# MB_Digital_and_Aanalog.net
KiCad netlist of a schematic drawn in EAGLE
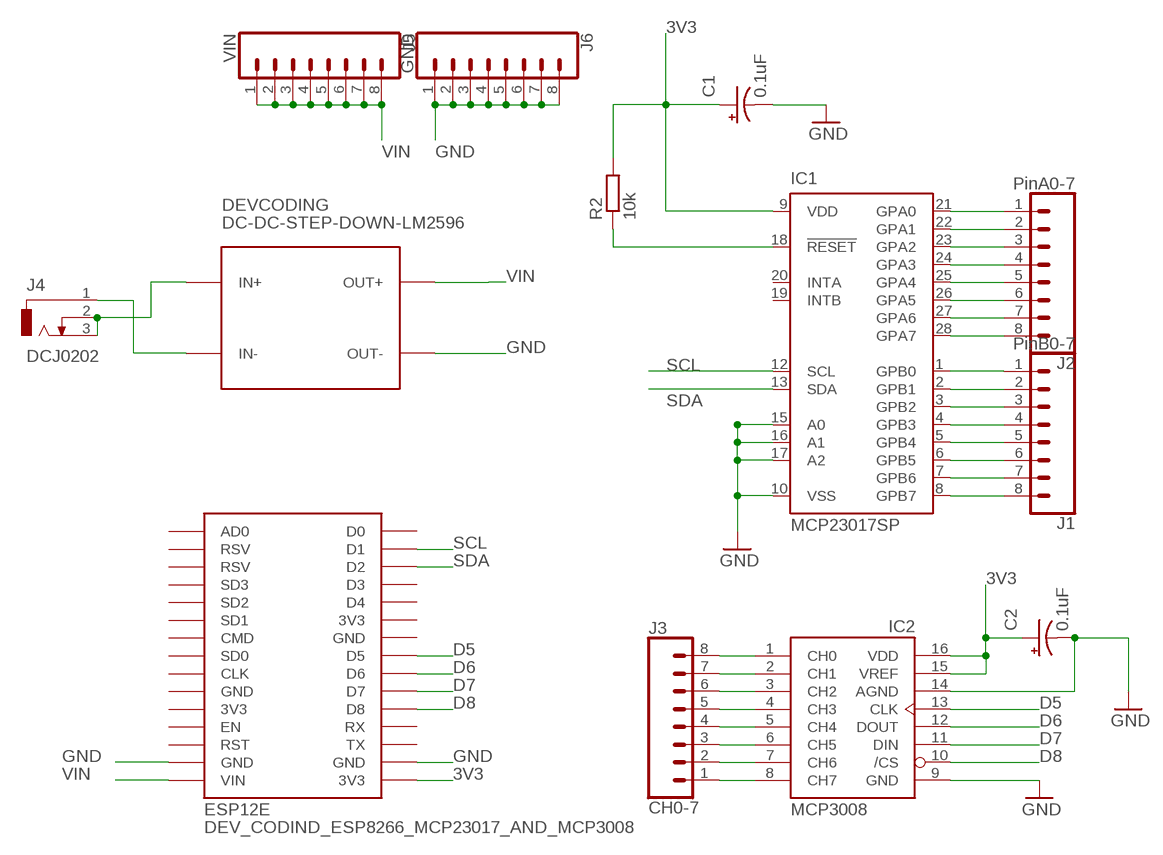
[diagram p0: schematic, sheet 1]

(export (version "E")
  (design (tool "Eeschema 10.0.6"))
  (components
    (comp (ref "C1")
      (value "0.1uF")
      (footprint "eagle-import:E1,8-4")
      (libsource (lib "eagle-import") (part "CPOL-USE1.8-4"))
    )
    (comp (ref "C2")
      (value "0.1uF")
      (footprint "eagle-import:E1,8-4")
      (libsource (lib "eagle-import") (part "CPOL-USE1.8-4"))
    )
    (comp (ref "DEVCODING")
      (value "DC-DC-STEP-DOWN-LM2596")
      (footprint "eagle-import:DC-DC-STEP-DOWN-LM2596")
      (libsource (lib "eagle-import") (part "DC-DC-STEP-DOWN-LM2596"))
    )
    (comp (ref "DEV_CODIND_ESP8266_MCP23017_AND_MCP3008")
      (value "ESP12E")
      (footprint "eagle-import:ESP12E_DEVKIT")
      (libsource (lib "eagle-import") (part "ESP12E_DEVKIT"))
    )
    (comp (ref "IC1")
      (value "MCP23017SP")
      (footprint "eagle-import:DIL28-3")
      (libsource (lib "eagle-import") (part "MCP23017SP"))
    )
    (comp (ref "IC2")
      (value "MCP3008")
      (footprint "eagle-import:DIL16")
      (libsource (lib "eagle-import") (part "MCP3008"))
    )
    (comp (ref "J1")
      (value "PinB0-7")
      (footprint "eagle-import:1X08_LONGPADS")
      (libsource (lib "eagle-import") (part "CONN_08LONGPADS"))
    )
    (comp (ref "J2")
      (value "PinA0-7")
      (footprint "eagle-import:1X08_LONGPADS")
      (libsource (lib "eagle-import") (part "CONN_08LONGPADS"))
    )
    (comp (ref "J3")
      (value "CH0-7")
      (footprint "eagle-import:1X08_LONGPADS")
      (libsource (lib "eagle-import") (part "CONN_08LONGPADS"))
    )
    (comp (ref "J4")
      (value "DCJ0202")
      (footprint "eagle-import:DCJ0202")
      (libsource (lib "eagle-import") (part "DCJ0202"))
    )
    (comp (ref "J5")
      (value "VIN")
      (footprint "eagle-import:1X08_LONGPADS")
      (libsource (lib "eagle-import") (part "CONN_08LONGPADS"))
    )
    (comp (ref "J6")
      (value "GND")
      (footprint "eagle-import:1X08_LONGPADS")
      (libsource (lib "eagle-import") (part "CONN_08LONGPADS"))
    )
    (comp (ref "R2")
      (value "10k")
      (footprint "eagle-import:0207_7")
      (libsource (lib "eagle-import") (part "R-EU_0207/7"))
    )
  )
  (nets
    (net (code "1") (name "/3V3") (class "Default")
      (node (ref "C1") (pin "+") (pinfunction "+_+") (pintype "passive"))
      (node (ref "C2") (pin "+") (pinfunction "+_+") (pintype "passive"))
      (node (ref "DEV_CODIND_ESP8266_MCP23017_AND_MCP3008") (pin "3V3@2") (pinfunction "3V3_3V3@2") (pintype "bidirectional"))
      (node (ref "IC1") (pin "9") (pinfunction "VDD_9") (pintype "power_in"))
      (node (ref "IC2") (pin "15") (pinfunction "VREF_15") (pintype "input"))
      (node (ref "IC2") (pin "16") (pinfunction "VDD_16") (pintype "power_in"))
      (node (ref "R2") (pin "2") (pinfunction "2_2") (pintype "passive"))
    )
    (net (code "2") (name "/D5") (class "Default")
      (node (ref "DEV_CODIND_ESP8266_MCP23017_AND_MCP3008") (pin "D5") (pinfunction "D5_D5") (pintype "bidirectional"))
      (node (ref "IC2") (pin "13") (pinfunction "CLK_13") (pintype "input"))
    )
    (net (code "3") (name "/D6") (class "Default")
      (node (ref "DEV_CODIND_ESP8266_MCP23017_AND_MCP3008") (pin "D6") (pinfunction "D6_D6") (pintype "bidirectional"))
      (node (ref "IC2") (pin "12") (pinfunction "DOUT_12") (pintype "output"))
    )
    (net (code "4") (name "/D7") (class "Default")
      (node (ref "DEV_CODIND_ESP8266_MCP23017_AND_MCP3008") (pin "D7") (pinfunction "D7_D7") (pintype "bidirectional"))
      (node (ref "IC2") (pin "11") (pinfunction "DIN_11") (pintype "input"))
    )
    (net (code "5") (name "/D8") (class "Default")
      (node (ref "DEV_CODIND_ESP8266_MCP23017_AND_MCP3008") (pin "D8") (pinfunction "D8_D8") (pintype "bidirectional"))
      (node (ref "IC2") (pin "10") (pinfunction "/CS_10") (pintype "input"))
    )
    (net (code "6") (name "/SCL") (class "Default")
      (node (ref "DEV_CODIND_ESP8266_MCP23017_AND_MCP3008") (pin "D1") (pinfunction "D1_D1") (pintype "bidirectional"))
      (node (ref "IC1") (pin "12") (pinfunction "SCL_12") (pintype "input"))
    )
    (net (code "7") (name "/SDA") (class "Default")
      (node (ref "DEV_CODIND_ESP8266_MCP23017_AND_MCP3008") (pin "D2") (pinfunction "D2_D2") (pintype "bidirectional"))
      (node (ref "IC1") (pin "13") (pinfunction "SDA_13") (pintype "bidirectional"))
    )
    (net (code "8") (name "/VIN") (class "Default")
      (node (ref "DEVCODING") (pin "OUT+") (pinfunction "OUT+_OUT+") (pintype "bidirectional"))
      (node (ref "DEV_CODIND_ESP8266_MCP23017_AND_MCP3008") (pin "VIN") (pinfunction "VIN_VIN") (pintype "bidirectional"))
      (node (ref "J5") (pin "1") (pinfunction "1_1") (pintype "passive"))
      (node (ref "J5") (pin "2") (pinfunction "2_2") (pintype "passive"))
      (node (ref "J5") (pin "3") (pinfunction "3_3") (pintype "passive"))
      (node (ref "J5") (pin "4") (pinfunction "4_4") (pintype "passive"))
      (node (ref "J5") (pin "5") (pinfunction "5_5") (pintype "passive"))
      (node (ref "J5") (pin "6") (pinfunction "6_6") (pintype "passive"))
      (node (ref "J5") (pin "7") (pinfunction "7_7") (pintype "passive"))
      (node (ref "J5") (pin "8") (pinfunction "8_8") (pintype "passive"))
    )
    (net (code "9") (name "GND") (class "Default")
      (node (ref "C1") (pin "-") (pinfunction "-_-") (pintype "passive"))
      (node (ref "C2") (pin "-") (pinfunction "-_-") (pintype "passive"))
      (node (ref "DEVCODING") (pin "OUT-") (pinfunction "OUT-_OUT-") (pintype "bidirectional"))
      (node (ref "DEV_CODIND_ESP8266_MCP23017_AND_MCP3008") (pin "GND@1") (pinfunction "GND_GND@1") (pintype "bidirectional"))
      (node (ref "DEV_CODIND_ESP8266_MCP23017_AND_MCP3008") (pin "GND@3") (pinfunction "GND_GND@3") (pintype "bidirectional"))
      (node (ref "IC1") (pin "10") (pinfunction "VSS_10") (pintype "power_in"))
      (node (ref "IC1") (pin "15") (pinfunction "A0_15") (pintype "input"))
      (node (ref "IC1") (pin "16") (pinfunction "A1_16") (pintype "input"))
      (node (ref "IC1") (pin "17") (pinfunction "A2_17") (pintype "input"))
      (node (ref "IC2") (pin "14") (pinfunction "AGND_14") (pintype "power_in"))
      (node (ref "IC2") (pin "9") (pinfunction "GND_9") (pintype "power_in"))
      (node (ref "J6") (pin "1") (pinfunction "1_1") (pintype "passive"))
      (node (ref "J6") (pin "2") (pinfunction "2_2") (pintype "passive"))
      (node (ref "J6") (pin "3") (pinfunction "3_3") (pintype "passive"))
      (node (ref "J6") (pin "4") (pinfunction "4_4") (pintype "passive"))
      (node (ref "J6") (pin "5") (pinfunction "5_5") (pintype "passive"))
      (node (ref "J6") (pin "6") (pinfunction "6_6") (pintype "passive"))
      (node (ref "J6") (pin "7") (pinfunction "7_7") (pintype "passive"))
      (node (ref "J6") (pin "8") (pinfunction "8_8") (pintype "passive"))
    )
    (net (code "10") (name "Net-(DEVCODING-PadIN+)") (class "Default")
      (node (ref "DEVCODING") (pin "IN+") (pinfunction "IN+_IN+") (pintype "bidirectional"))
      (node (ref "J4") (pin "2") (pinfunction "2_2") (pintype "passive"))
      (node (ref "J4") (pin "3") (pinfunction "3_3") (pintype "passive"))
    )
    (net (code "11") (name "Net-(DEVCODING-PadIN-)") (class "Default")
      (node (ref "DEVCODING") (pin "IN-") (pinfunction "IN-_IN-") (pintype "bidirectional"))
      (node (ref "J4") (pin "1") (pinfunction "1_1") (pintype "passive"))
    )
    (net (code "12") (name "Net-(IC1-GPA0)") (class "Default")
      (node (ref "IC1") (pin "21") (pinfunction "GPA0_21") (pintype "bidirectional"))
      (node (ref "J2") (pin "1") (pinfunction "1_1") (pintype "passive"))
    )
    (net (code "13") (name "Net-(IC1-GPA1)") (class "Default")
      (node (ref "IC1") (pin "22") (pinfunction "GPA1_22") (pintype "bidirectional"))
      (node (ref "J2") (pin "2") (pinfunction "2_2") (pintype "passive"))
    )
    (net (code "14") (name "Net-(IC1-GPA2)") (class "Default")
      (node (ref "IC1") (pin "23") (pinfunction "GPA2_23") (pintype "bidirectional"))
      (node (ref "J2") (pin "3") (pinfunction "3_3") (pintype "passive"))
    )
    (net (code "15") (name "Net-(IC1-GPA3)") (class "Default")
      (node (ref "IC1") (pin "24") (pinfunction "GPA3_24") (pintype "bidirectional"))
      (node (ref "J2") (pin "4") (pinfunction "4_4") (pintype "passive"))
    )
    (net (code "16") (name "Net-(IC1-GPA4)") (class "Default")
      (node (ref "IC1") (pin "25") (pinfunction "GPA4_25") (pintype "bidirectional"))
      (node (ref "J2") (pin "5") (pinfunction "5_5") (pintype "passive"))
    )
    (net (code "17") (name "Net-(IC1-GPA5)") (class "Default")
      (node (ref "IC1") (pin "26") (pinfunction "GPA5_26") (pintype "bidirectional"))
      (node (ref "J2") (pin "6") (pinfunction "6_6") (pintype "passive"))
    )
    (net (code "18") (name "Net-(IC1-GPA6)") (class "Default")
      (node (ref "IC1") (pin "27") (pinfunction "GPA6_27") (pintype "bidirectional"))
      (node (ref "J2") (pin "7") (pinfunction "7_7") (pintype "passive"))
    )
    (net (code "19") (name "Net-(IC1-GPA7)") (class "Default")
      (node (ref "IC1") (pin "28") (pinfunction "GPA7_28") (pintype "bidirectional"))
      (node (ref "J2") (pin "8") (pinfunction "8_8") (pintype "passive"))
    )
    (net (code "20") (name "Net-(IC1-GPB0)") (class "Default")
      (node (ref "IC1") (pin "1") (pinfunction "GPB0_1") (pintype "bidirectional"))
      (node (ref "J1") (pin "1") (pinfunction "1_1") (pintype "passive"))
    )
    (net (code "21") (name "Net-(IC1-GPB1)") (class "Default")
      (node (ref "IC1") (pin "2") (pinfunction "GPB1_2") (pintype "bidirectional"))
      (node (ref "J1") (pin "2") (pinfunction "2_2") (pintype "passive"))
    )
    (net (code "22") (name "Net-(IC1-GPB2)") (class "Default")
      (node (ref "IC1") (pin "3") (pinfunction "GPB2_3") (pintype "bidirectional"))
      (node (ref "J1") (pin "3") (pinfunction "3_3") (pintype "passive"))
    )
    (net (code "23") (name "Net-(IC1-GPB3)") (class "Default")
      (node (ref "IC1") (pin "4") (pinfunction "GPB3_4") (pintype "bidirectional"))
      (node (ref "J1") (pin "4") (pinfunction "4_4") (pintype "passive"))
    )
    (net (code "24") (name "Net-(IC1-GPB4)") (class "Default")
      (node (ref "IC1") (pin "5") (pinfunction "GPB4_5") (pintype "bidirectional"))
      (node (ref "J1") (pin "5") (pinfunction "5_5") (pintype "passive"))
    )
    (net (code "25") (name "Net-(IC1-GPB5)") (class "Default")
      (node (ref "IC1") (pin "6") (pinfunction "GPB5_6") (pintype "bidirectional"))
      (node (ref "J1") (pin "6") (pinfunction "6_6") (pintype "passive"))
    )
    (net (code "26") (name "Net-(IC1-GPB6)") (class "Default")
      (node (ref "IC1") (pin "7") (pinfunction "GPB6_7") (pintype "bidirectional"))
      (node (ref "J1") (pin "7") (pinfunction "7_7") (pintype "passive"))
    )
    (net (code "27") (name "Net-(IC1-GPB7)") (class "Default")
      (node (ref "IC1") (pin "8") (pinfunction "GPB7_8") (pintype "bidirectional"))
      (node (ref "J1") (pin "8") (pinfunction "8_8") (pintype "passive"))
    )
    (net (code "28") (name "Net-(IC1-~{RESET})") (class "Default")
      (node (ref "IC1") (pin "18") (pinfunction "~{RESET}_18") (pintype "input"))
      (node (ref "R2") (pin "1") (pinfunction "1_1") (pintype "passive"))
    )
    (net (code "29") (name "Net-(IC2-CH0)") (class "Default")
      (node (ref "IC2") (pin "1") (pinfunction "CH0_1") (pintype "input"))
      (node (ref "J3") (pin "8") (pinfunction "8_8") (pintype "passive"))
    )
    (net (code "30") (name "Net-(IC2-CH1)") (class "Default")
      (node (ref "IC2") (pin "2") (pinfunction "CH1_2") (pintype "input"))
      (node (ref "J3") (pin "7") (pinfunction "7_7") (pintype "passive"))
    )
    (net (code "31") (name "Net-(IC2-CH2)") (class "Default")
      (node (ref "IC2") (pin "3") (pinfunction "CH2_3") (pintype "input"))
      (node (ref "J3") (pin "6") (pinfunction "6_6") (pintype "passive"))
    )
    (net (code "32") (name "Net-(IC2-CH3)") (class "Default")
      (node (ref "IC2") (pin "4") (pinfunction "CH3_4") (pintype "input"))
      (node (ref "J3") (pin "5") (pinfunction "5_5") (pintype "passive"))
    )
    (net (code "33") (name "Net-(IC2-CH4)") (class "Default")
      (node (ref "IC2") (pin "5") (pinfunction "CH4_5") (pintype "input"))
      (node (ref "J3") (pin "4") (pinfunction "4_4") (pintype "passive"))
    )
    (net (code "34") (name "Net-(IC2-CH5)") (class "Default")
      (node (ref "IC2") (pin "6") (pinfunction "CH5_6") (pintype "input"))
      (node (ref "J3") (pin "3") (pinfunction "3_3") (pintype "passive"))
    )
    (net (code "35") (name "Net-(IC2-CH6)") (class "Default")
      (node (ref "IC2") (pin "7") (pinfunction "CH6_7") (pintype "input"))
      (node (ref "J3") (pin "2") (pinfunction "2_2") (pintype "passive"))
    )
    (net (code "36") (name "Net-(IC2-CH7)") (class "Default")
      (node (ref "IC2") (pin "8") (pinfunction "CH7_8") (pintype "input"))
      (node (ref "J3") (pin "1") (pinfunction "1_1") (pintype "passive"))
    )
    (net (code "37") (name "unconnected-(DEV_CODIND_ESP8266_MCP23017_AND_MCP3008-3V3-Pad3V3@0)") (class "Default")
      (node (ref "DEV_CODIND_ESP8266_MCP23017_AND_MCP3008") (pin "3V3@0") (pinfunction "3V3_3V3@0") (pintype "bidirectional"))
    )
    (net (code "38") (name "unconnected-(DEV_CODIND_ESP8266_MCP23017_AND_MCP3008-3V3-Pad3V3@1)") (class "Default")
      (node (ref "DEV_CODIND_ESP8266_MCP23017_AND_MCP3008") (pin "3V3@1") (pinfunction "3V3_3V3@1") (pintype "bidirectional"))
    )
    (net (code "39") (name "unconnected-(DEV_CODIND_ESP8266_MCP23017_AND_MCP3008-GND-PadGND@0)") (class "Default")
      (node (ref "DEV_CODIND_ESP8266_MCP23017_AND_MCP3008") (pin "GND@0") (pinfunction "GND_GND@0") (pintype "bidirectional"))
    )
    (net (code "40") (name "unconnected-(DEV_CODIND_ESP8266_MCP23017_AND_MCP3008-GND-PadGND@2)") (class "Default")
      (node (ref "DEV_CODIND_ESP8266_MCP23017_AND_MCP3008") (pin "GND@2") (pinfunction "GND_GND@2") (pintype "bidirectional"))
    )
    (net (code "41") (name "unconnected-(DEV_CODIND_ESP8266_MCP23017_AND_MCP3008-PadAD0)") (class "Default")
      (node (ref "DEV_CODIND_ESP8266_MCP23017_AND_MCP3008") (pin "AD0") (pinfunction "AD0_AD0") (pintype "bidirectional"))
    )
    (net (code "42") (name "unconnected-(DEV_CODIND_ESP8266_MCP23017_AND_MCP3008-PadCLK)") (class "Default")
      (node (ref "DEV_CODIND_ESP8266_MCP23017_AND_MCP3008") (pin "CLK") (pinfunction "CLK_CLK") (pintype "bidirectional"))
    )
    (net (code "43") (name "unconnected-(DEV_CODIND_ESP8266_MCP23017_AND_MCP3008-PadCMD)") (class "Default")
      (node (ref "DEV_CODIND_ESP8266_MCP23017_AND_MCP3008") (pin "CMD") (pinfunction "CMD_CMD") (pintype "bidirectional"))
    )
    (net (code "44") (name "unconnected-(DEV_CODIND_ESP8266_MCP23017_AND_MCP3008-PadD0)") (class "Default")
      (node (ref "DEV_CODIND_ESP8266_MCP23017_AND_MCP3008") (pin "D0") (pinfunction "D0_D0") (pintype "bidirectional"))
    )
    (net (code "45") (name "unconnected-(DEV_CODIND_ESP8266_MCP23017_AND_MCP3008-PadD3)") (class "Default")
      (node (ref "DEV_CODIND_ESP8266_MCP23017_AND_MCP3008") (pin "D3") (pinfunction "D3_D3") (pintype "bidirectional"))
    )
    (net (code "46") (name "unconnected-(DEV_CODIND_ESP8266_MCP23017_AND_MCP3008-PadD4)") (class "Default")
      (node (ref "DEV_CODIND_ESP8266_MCP23017_AND_MCP3008") (pin "D4") (pinfunction "D4_D4") (pintype "bidirectional"))
    )
    (net (code "47") (name "unconnected-(DEV_CODIND_ESP8266_MCP23017_AND_MCP3008-PadEN)") (class "Default")
      (node (ref "DEV_CODIND_ESP8266_MCP23017_AND_MCP3008") (pin "EN") (pinfunction "EN_EN") (pintype "bidirectional"))
    )
    (net (code "48") (name "unconnected-(DEV_CODIND_ESP8266_MCP23017_AND_MCP3008-PadRST)") (class "Default")
      (node (ref "DEV_CODIND_ESP8266_MCP23017_AND_MCP3008") (pin "RST") (pinfunction "RST_RST") (pintype "bidirectional"))
    )
    (net (code "49") (name "unconnected-(DEV_CODIND_ESP8266_MCP23017_AND_MCP3008-PadRX)") (class "Default")
      (node (ref "DEV_CODIND_ESP8266_MCP23017_AND_MCP3008") (pin "RX") (pinfunction "RX_RX") (pintype "bidirectional"))
    )
    (net (code "50") (name "unconnected-(DEV_CODIND_ESP8266_MCP23017_AND_MCP3008-PadSD0)") (class "Default")
      (node (ref "DEV_CODIND_ESP8266_MCP23017_AND_MCP3008") (pin "SD0") (pinfunction "SD0_SD0") (pintype "bidirectional"))
    )
    (net (code "51") (name "unconnected-(DEV_CODIND_ESP8266_MCP23017_AND_MCP3008-PadSD1)") (class "Default")
      (node (ref "DEV_CODIND_ESP8266_MCP23017_AND_MCP3008") (pin "SD1") (pinfunction "SD1_SD1") (pintype "bidirectional"))
    )
    (net (code "52") (name "unconnected-(DEV_CODIND_ESP8266_MCP23017_AND_MCP3008-PadSD2)") (class "Default")
      (node (ref "DEV_CODIND_ESP8266_MCP23017_AND_MCP3008") (pin "SD2") (pinfunction "SD2_SD2") (pintype "bidirectional"))
    )
    (net (code "53") (name "unconnected-(DEV_CODIND_ESP8266_MCP23017_AND_MCP3008-PadSD3)") (class "Default")
      (node (ref "DEV_CODIND_ESP8266_MCP23017_AND_MCP3008") (pin "SD3") (pinfunction "SD3_SD3") (pintype "bidirectional"))
    )
    (net (code "54") (name "unconnected-(DEV_CODIND_ESP8266_MCP23017_AND_MCP3008-PadTX)") (class "Default")
      (node (ref "DEV_CODIND_ESP8266_MCP23017_AND_MCP3008") (pin "TX") (pinfunction "TX_TX") (pintype "bidirectional"))
    )
    (net (code "55") (name "unconnected-(DEV_CODIND_ESP8266_MCP23017_AND_MCP3008-RSV-PadRSV@0)") (class "Default")
      (node (ref "DEV_CODIND_ESP8266_MCP23017_AND_MCP3008") (pin "RSV@0") (pinfunction "RSV_RSV@0") (pintype "bidirectional"))
    )
    (net (code "56") (name "unconnected-(DEV_CODIND_ESP8266_MCP23017_AND_MCP3008-RSV-PadRSV@1)") (class "Default")
      (node (ref "DEV_CODIND_ESP8266_MCP23017_AND_MCP3008") (pin "RSV@1") (pinfunction "RSV_RSV@1") (pintype "bidirectional"))
    )
    (net (code "57") (name "unconnected-(IC1-INTA-Pad20)") (class "Default")
      (node (ref "IC1") (pin "20") (pinfunction "INTA_20") (pintype "output"))
    )
    (net (code "58") (name "unconnected-(IC1-INTB-Pad19)") (class "Default")
      (node (ref "IC1") (pin "19") (pinfunction "INTB_19") (pintype "output"))
    )
  )
)
